# -_PSU.net
KiCad netlist of a schematic drawn in EAGLE
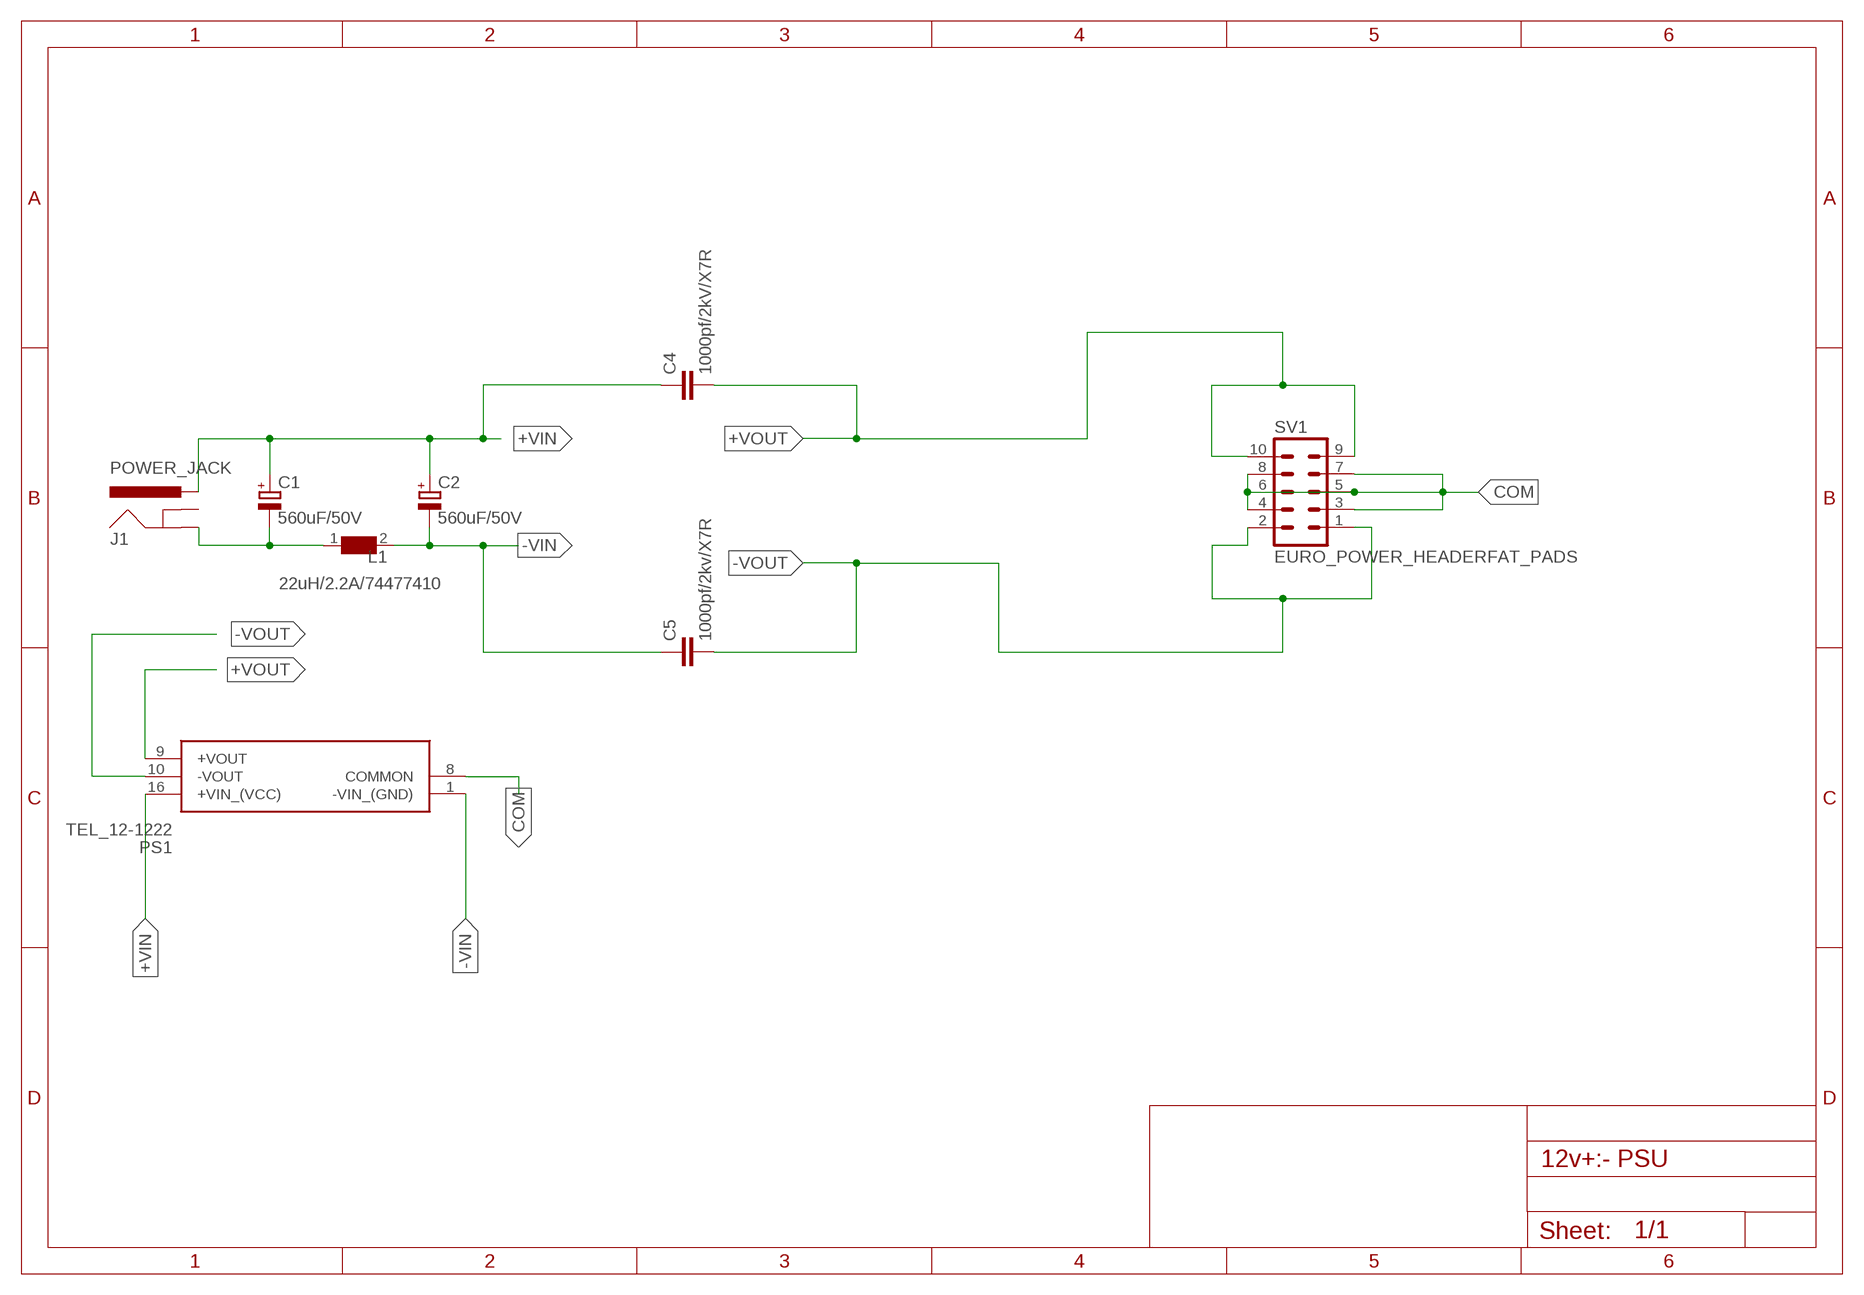
[diagram p0: schematic, sheet 1]

(export (version "E")
  (design (tool "Eeschema 10.0.6"))
  (components
    (comp (ref "C1")
      (value "560uF/50V")
      (footprint "eagle-import:E7,5-16")
      (libsource (lib "eagle-import") (part "CPOL-EUE7.5-16"))
    )
    (comp (ref "C2")
      (value "560uF/50V")
      (footprint "eagle-import:E7,5-16")
      (libsource (lib "eagle-import") (part "CPOL-EUE7.5-16"))
    )
    (comp (ref "C4")
      (value "1000pf/2kV/X7R")
      (footprint "eagle-import:C0805")
      (libsource (lib "eagle-import") (part "C-EUC0805"))
    )
    (comp (ref "C5")
      (value "1000pf/2kv/X7R")
      (footprint "eagle-import:C0805")
      (libsource (lib "eagle-import") (part "C-EUC0805"))
    )
    (comp (ref "J1")
      (value "POWER_JACK")
      (footprint "eagle-import:POWER_JACK_PTH")
      (libsource (lib "eagle-import") (part "POWER_JACK"))
    )
    (comp (ref "L1")
      (value "22uH/2.2A/74477410")
      (footprint "eagle-import:WE-PD2_5848_5820")
      (fields (field (name "MPN") "74477410"))
      (libsource (lib "eagle-import") (part "WE-PD2_5848/5820-74477410"))
    )
    (comp (ref "PS1")
      (value "TEL_12-1222")
      (footprint "eagle-import:TEL121222")
      (fields
        (field (name "MANUFACTURER_PART_NUMBER") "TEL 12-1222")
        (field (name "MOUSER_PART_NUMBER") "495-TEL12-1222")
      )
      (libsource (lib "eagle-import") (part "TEL_12-1222"))
    )
    (comp (ref "SV1")
      (value "EURO_POWER_HEADERFAT_PADS")
      (footprint "eagle-import:EURO_PWR_HEADER_FAT")
      (libsource (lib "eagle-import") (part "EURO_POWER_HEADERFAT_PADS"))
    )
  )
  (nets
    (net (code "1") (name "+VIN") (class "Default")
      (node (ref "C1") (pin "+") (pinfunction "+_+") (pintype "passive"))
      (node (ref "C2") (pin "+") (pinfunction "+_+") (pintype "passive"))
      (node (ref "C4") (pin "1") (pinfunction "1_1") (pintype "passive"))
      (node (ref "J1") (pin "PWR") (pinfunction "PWR_PWR") (pintype "bidirectional"))
      (node (ref "PS1") (pin "16") (pinfunction "+VIN_(VCC)_16") (pintype "bidirectional"))
    )
    (net (code "2") (name "+VOUT") (class "Default")
      (node (ref "C4") (pin "2") (pinfunction "2_2") (pintype "passive"))
      (node (ref "PS1") (pin "9") (pinfunction "+VOUT_9") (pintype "bidirectional"))
      (node (ref "SV1") (pin "10") (pinfunction "10_10") (pintype "passive"))
      (node (ref "SV1") (pin "9") (pinfunction "9_9") (pintype "passive"))
    )
    (net (code "3") (name "-VIN") (class "Default")
      (node (ref "C2") (pin "-") (pinfunction "-_-") (pintype "passive"))
      (node (ref "C5") (pin "1") (pinfunction "1_1") (pintype "passive"))
      (node (ref "L1") (pin "2") (pinfunction "2_2") (pintype "passive"))
      (node (ref "PS1") (pin "1") (pinfunction "-VIN_(GND)_1") (pintype "bidirectional"))
    )
    (net (code "4") (name "-VOUT") (class "Default")
      (node (ref "C5") (pin "2") (pinfunction "2_2") (pintype "passive"))
      (node (ref "PS1") (pin "10") (pinfunction "-VOUT_10") (pintype "bidirectional"))
      (node (ref "SV1") (pin "1") (pinfunction "1_1") (pintype "passive"))
      (node (ref "SV1") (pin "2") (pinfunction "2_2") (pintype "passive"))
    )
    (net (code "5") (name "COM") (class "Default")
      (node (ref "PS1") (pin "8") (pinfunction "COMMON_8") (pintype "bidirectional"))
      (node (ref "SV1") (pin "3") (pinfunction "3_3") (pintype "passive"))
      (node (ref "SV1") (pin "4") (pinfunction "4_4") (pintype "passive"))
      (node (ref "SV1") (pin "5") (pinfunction "5_5") (pintype "passive"))
      (node (ref "SV1") (pin "6") (pinfunction "6_6") (pintype "passive"))
      (node (ref "SV1") (pin "7") (pinfunction "7_7") (pintype "passive"))
      (node (ref "SV1") (pin "8") (pinfunction "8_8") (pintype "passive"))
    )
    (net (code "6") (name "Net-(C1-Pad-)") (class "Default")
      (node (ref "C1") (pin "-") (pinfunction "-_-") (pintype "passive"))
      (node (ref "J1") (pin "GND") (pinfunction "GND_GND") (pintype "bidirectional"))
      (node (ref "L1") (pin "1") (pinfunction "1_1") (pintype "passive"))
    )
    (net (code "7") (name "unconnected-(J1-PadGNDBREAK)") (class "Default")
      (node (ref "J1") (pin "GNDBREAK") (pinfunction "GNDBREAK_GNDBREAK") (pintype "bidirectional"))
    )
  )
)
